# DigitalLabBoard_Stepper.net
KiCad netlist of a schematic drawn in Altium Designer
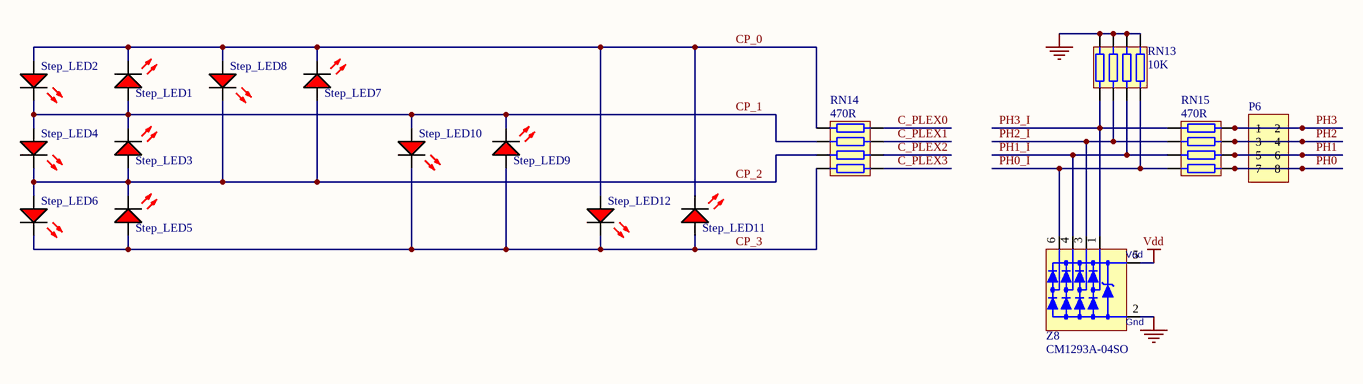
[diagram p0: DigitalLabBoard_Stepper.SchDoc]

(export (version "E")
  (design (tool "Eeschema 10.0.6"))
  (components
    (comp (ref "P6")
      (value "Header 2x4")
      (footprint "HDR2X4S")
      (libsource (lib "MyLibrary") (part "Header 2x4"))
    )
    (comp (ref "RN13")
      (value "10K")
      (footprint "CR1206-0603_X4_N")
      (description "SMT x4 Resistor Array")
      (libsource (lib "") (part "ResistorNetwork_CR0603x4_2"))
    )
    (comp (ref "RN14")
      (value "470R")
      (footprint "CR1206-0603_X4_N")
      (description "SMT x4 Resistor Array")
      (libsource (lib "") (part "ResistorNetwork_CR0603x4_1"))
    )
    (comp (ref "RN15")
      (value "470R")
      (footprint "CR1206-0603_X4_N")
      (description "SMT x4 Resistor Array")
      (libsource (lib "MyLibrary") (part "ResistorNetwork_CR0603x4"))
    )
    (comp (ref "Step_LED1")
      (value "LED Red")
      (footprint "LED1608-0603-RED")
      (description "LED 0603 Red")
      (fields (field (name "MANUFACTURER") "Generic Components") (field (name "PUBLISHER") "Altium Limited"))
      (libsource (lib "MySchLib") (part "LED-0603-Red"))
    )
    (comp (ref "Step_LED2")
      (value "LED Red")
      (footprint "LED1608-0603-RED")
      (description "LED 0603 Red")
      (fields (field (name "MANUFACTURER") "Generic Components") (field (name "PUBLISHER") "Altium Limited"))
      (libsource (lib "MySchLib") (part "LED-0603-Red"))
    )
    (comp (ref "Step_LED3")
      (value "LED Red")
      (footprint "LED1608-0603-RED")
      (description "LED 0603 Red")
      (fields (field (name "MANUFACTURER") "Generic Components") (field (name "PUBLISHER") "Altium Limited"))
      (libsource (lib "MySchLib") (part "LED-0603-Red"))
    )
    (comp (ref "Step_LED4")
      (value "LED Red")
      (footprint "LED1608-0603-RED")
      (description "LED 0603 Red")
      (fields (field (name "MANUFACTURER") "Generic Components") (field (name "PUBLISHER") "Altium Limited"))
      (libsource (lib "MySchLib") (part "LED-0603-Red"))
    )
    (comp (ref "Step_LED5")
      (value "LED Red")
      (footprint "LED1608-0603-RED")
      (description "LED 0603 Red")
      (fields (field (name "MANUFACTURER") "Generic Components") (field (name "PUBLISHER") "Altium Limited"))
      (libsource (lib "MySchLib") (part "LED-0603-Red"))
    )
    (comp (ref "Step_LED6")
      (value "LED Red")
      (footprint "LED1608-0603-RED")
      (description "LED 0603 Red")
      (fields (field (name "MANUFACTURER") "Generic Components") (field (name "PUBLISHER") "Altium Limited"))
      (libsource (lib "MySchLib") (part "LED-0603-Red"))
    )
    (comp (ref "Step_LED7")
      (value "LED Red")
      (footprint "LED1608-0603-RED")
      (description "LED 0603 Red")
      (fields (field (name "MANUFACTURER") "Generic Components") (field (name "PUBLISHER") "Altium Limited"))
      (libsource (lib "MySchLib") (part "LED-0603-Red"))
    )
    (comp (ref "Step_LED8")
      (value "LED Red")
      (footprint "LED1608-0603-RED")
      (description "LED 0603 Red")
      (fields (field (name "MANUFACTURER") "Generic Components") (field (name "PUBLISHER") "Altium Limited"))
      (libsource (lib "MySchLib") (part "LED-0603-Red"))
    )
    (comp (ref "Step_LED9")
      (value "LED Red")
      (footprint "LED1608-0603-RED")
      (description "LED 0603 Red")
      (fields (field (name "MANUFACTURER") "Generic Components") (field (name "PUBLISHER") "Altium Limited"))
      (libsource (lib "MySchLib") (part "LED-0603-Red"))
    )
    (comp (ref "Step_LED10")
      (value "LED Red")
      (footprint "LED1608-0603-RED")
      (description "LED 0603 Red")
      (fields (field (name "MANUFACTURER") "Generic Components") (field (name "PUBLISHER") "Altium Limited"))
      (libsource (lib "MySchLib") (part "LED-0603-Red"))
    )
    (comp (ref "Step_LED11")
      (value "LED Red")
      (footprint "LED1608-0603-RED")
      (description "LED 0603 Red")
      (fields (field (name "MANUFACTURER") "Generic Components") (field (name "PUBLISHER") "Altium Limited"))
      (libsource (lib "MySchLib") (part "LED-0603-Red"))
    )
    (comp (ref "Step_LED12")
      (value "LED Red")
      (footprint "LED1608-0603-RED")
      (description "LED 0603 Red")
      (fields (field (name "MANUFACTURER") "Generic Components") (field (name "PUBLISHER") "Altium Limited"))
      (libsource (lib "MySchLib") (part "LED-0603-Red"))
    )
    (comp (ref "Z8")
      (value "CM1293A-04SO")
      (footprint "SOT457_N")
      (description "Ultra low capacitance quadruple rail-to-rail ESD protection")
      (libsource (lib "MySchLib") (part "CM1293A-04SO"))
    )
  )
  (nets
    (net (code "1") (name "/CP_0") (class "Default")
      (node (ref "RN14") (pin "5") (pinfunction "5_5") (pintype "passive"))
      (node (ref "Step_LED1") (pin "K") (pinfunction "K_K") (pintype "passive"))
      (node (ref "Step_LED11") (pin "K") (pinfunction "K_K") (pintype "passive"))
      (node (ref "Step_LED12") (pin "A") (pinfunction "A_A") (pintype "passive"))
      (node (ref "Step_LED2") (pin "A") (pinfunction "A_A") (pintype "passive"))
      (node (ref "Step_LED7") (pin "K") (pinfunction "K_K") (pintype "passive"))
      (node (ref "Step_LED8") (pin "A") (pinfunction "A_A") (pintype "passive"))
    )
    (net (code "2") (name "/CP_1") (class "Default")
      (node (ref "RN14") (pin "6") (pinfunction "6_6") (pintype "passive"))
      (node (ref "Step_LED1") (pin "A") (pinfunction "A_A") (pintype "passive"))
      (node (ref "Step_LED10") (pin "A") (pinfunction "A_A") (pintype "passive"))
      (node (ref "Step_LED2") (pin "K") (pinfunction "K_K") (pintype "passive"))
      (node (ref "Step_LED3") (pin "K") (pinfunction "K_K") (pintype "passive"))
      (node (ref "Step_LED4") (pin "A") (pinfunction "A_A") (pintype "passive"))
      (node (ref "Step_LED9") (pin "K") (pinfunction "K_K") (pintype "passive"))
    )
    (net (code "3") (name "/CP_2") (class "Default")
      (node (ref "RN14") (pin "7") (pinfunction "7_7") (pintype "passive"))
      (node (ref "Step_LED3") (pin "A") (pinfunction "A_A") (pintype "passive"))
      (node (ref "Step_LED4") (pin "K") (pinfunction "K_K") (pintype "passive"))
      (node (ref "Step_LED5") (pin "K") (pinfunction "K_K") (pintype "passive"))
      (node (ref "Step_LED6") (pin "A") (pinfunction "A_A") (pintype "passive"))
      (node (ref "Step_LED7") (pin "A") (pinfunction "A_A") (pintype "passive"))
      (node (ref "Step_LED8") (pin "K") (pinfunction "K_K") (pintype "passive"))
    )
    (net (code "4") (name "/CP_3") (class "Default")
      (node (ref "RN14") (pin "8") (pinfunction "8_8") (pintype "passive"))
      (node (ref "Step_LED10") (pin "K") (pinfunction "K_K") (pintype "passive"))
      (node (ref "Step_LED11") (pin "A") (pinfunction "A_A") (pintype "passive"))
      (node (ref "Step_LED12") (pin "K") (pinfunction "K_K") (pintype "passive"))
      (node (ref "Step_LED5") (pin "A") (pinfunction "A_A") (pintype "passive"))
      (node (ref "Step_LED6") (pin "K") (pinfunction "K_K") (pintype "passive"))
      (node (ref "Step_LED9") (pin "A") (pinfunction "A_A") (pintype "passive"))
    )
    (net (code "5") (name "/C_PLEX0") (class "Default")
      (node (ref "RN14") (pin "4") (pinfunction "4_4") (pintype "passive"))
    )
    (net (code "6") (name "/C_PLEX1") (class "Default")
      (node (ref "RN14") (pin "3") (pinfunction "3_3") (pintype "passive"))
    )
    (net (code "7") (name "/C_PLEX2") (class "Default")
      (node (ref "RN14") (pin "2") (pinfunction "2_2") (pintype "passive"))
    )
    (net (code "8") (name "/C_PLEX3") (class "Default")
      (node (ref "RN14") (pin "1") (pinfunction "1_1") (pintype "passive"))
    )
    (net (code "9") (name "/PH0") (class "Default")
      (node (ref "P6") (pin "7") (pinfunction "7_7") (pintype "passive"))
      (node (ref "P6") (pin "8") (pinfunction "8_8") (pintype "passive"))
      (node (ref "RN15") (pin "8") (pinfunction "8_8") (pintype "passive"))
    )
    (net (code "10") (name "/PH0_I") (class "Default")
      (node (ref "RN13") (pin "8") (pinfunction "8_8") (pintype "passive"))
      (node (ref "RN15") (pin "1") (pinfunction "1_1") (pintype "passive"))
      (node (ref "Z8") (pin "6") (pintype "passive"))
    )
    (net (code "11") (name "/PH1") (class "Default")
      (node (ref "P6") (pin "5") (pinfunction "5_5") (pintype "passive"))
      (node (ref "P6") (pin "6") (pinfunction "6_6") (pintype "passive"))
      (node (ref "RN15") (pin "7") (pinfunction "7_7") (pintype "passive"))
    )
    (net (code "12") (name "/PH1_I") (class "Default")
      (node (ref "RN13") (pin "7") (pinfunction "7_7") (pintype "passive"))
      (node (ref "RN15") (pin "2") (pinfunction "2_2") (pintype "passive"))
      (node (ref "Z8") (pin "4") (pintype "passive"))
    )
    (net (code "13") (name "/PH2") (class "Default")
      (node (ref "P6") (pin "3") (pinfunction "3_3") (pintype "passive"))
      (node (ref "P6") (pin "4") (pinfunction "4_4") (pintype "passive"))
      (node (ref "RN15") (pin "6") (pinfunction "6_6") (pintype "passive"))
    )
    (net (code "14") (name "/PH2_I") (class "Default")
      (node (ref "RN13") (pin "6") (pinfunction "6_6") (pintype "passive"))
      (node (ref "RN15") (pin "3") (pinfunction "3_3") (pintype "passive"))
      (node (ref "Z8") (pin "3") (pintype "passive"))
    )
    (net (code "15") (name "/PH3") (class "Default")
      (node (ref "P6") (pin "1") (pinfunction "1_1") (pintype "passive"))
      (node (ref "P6") (pin "2") (pinfunction "2_2") (pintype "passive"))
      (node (ref "RN15") (pin "5") (pinfunction "5_5") (pintype "passive"))
    )
    (net (code "16") (name "/PH3_I") (class "Default")
      (node (ref "RN13") (pin "5") (pinfunction "5_5") (pintype "passive"))
      (node (ref "RN15") (pin "4") (pinfunction "4_4") (pintype "passive"))
      (node (ref "Z8") (pin "1") (pintype "passive"))
    )
    (net (code "17") (name "GND") (class "Default")
      (node (ref "RN13") (pin "1") (pinfunction "1_1") (pintype "passive"))
      (node (ref "RN13") (pin "2") (pinfunction "2_2") (pintype "passive"))
      (node (ref "RN13") (pin "3") (pinfunction "3_3") (pintype "passive"))
      (node (ref "RN13") (pin "4") (pinfunction "4_4") (pintype "passive"))
      (node (ref "Z8") (pin "2") (pinfunction "Vn_2") (pintype "passive"))
    )
    (net (code "18") (name "Vdd") (class "Default")
      (node (ref "Z8") (pin "5") (pinfunction "Vp_5") (pintype "passive"))
    )
  )
)
